# LifeBoardV1.net
KiCad netlist of a schematic drawn in EAGLE
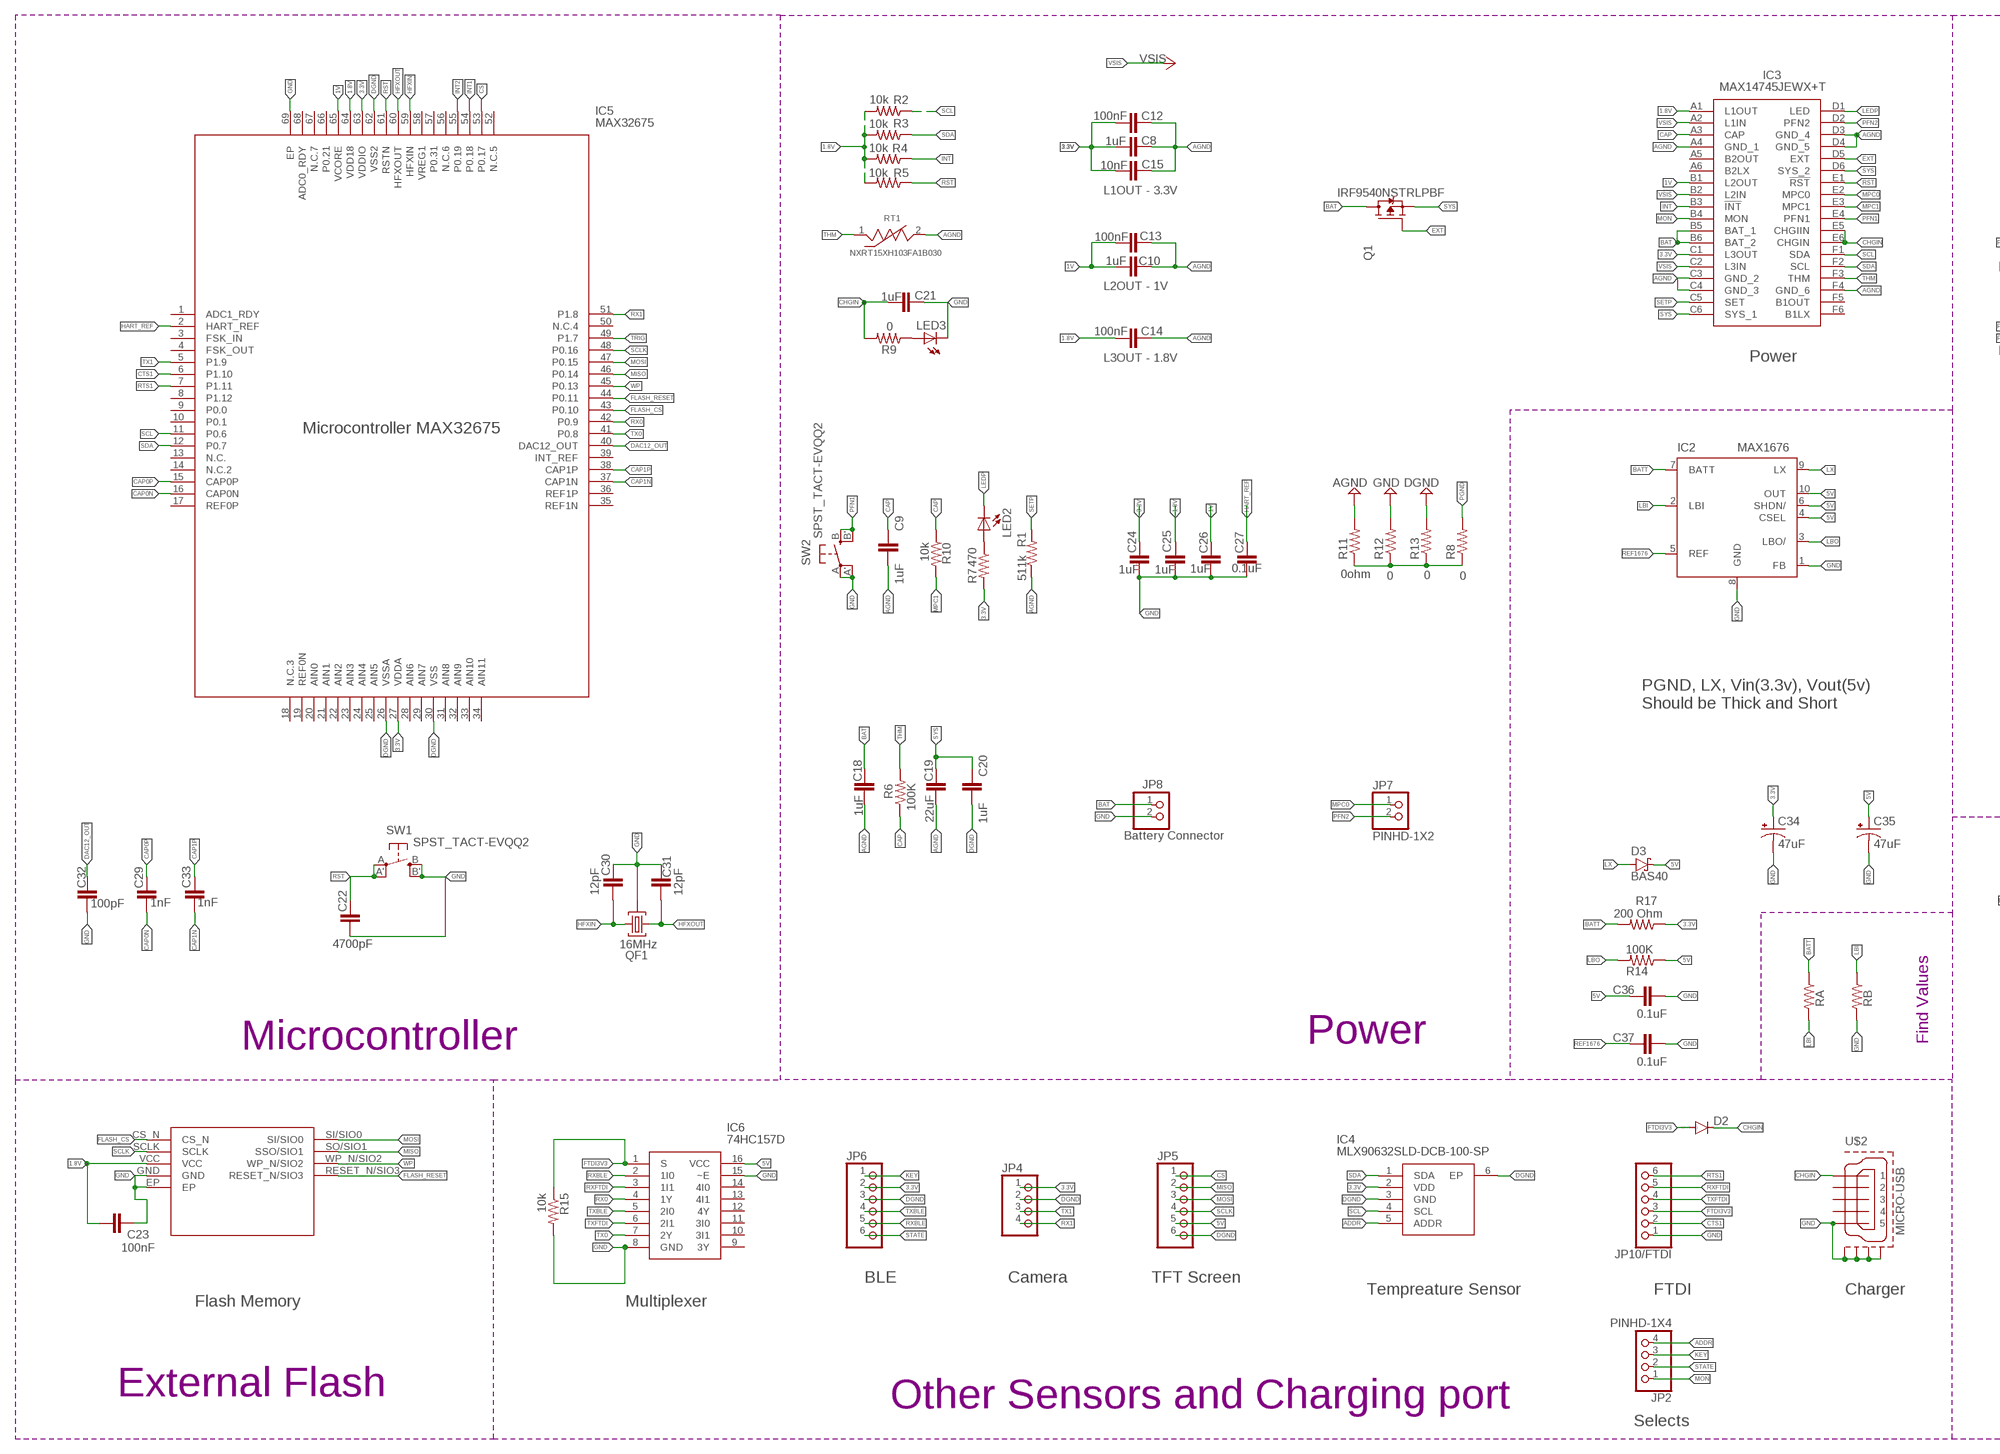
[diagram p0: schematic, sheet 1, part 1 of 2]
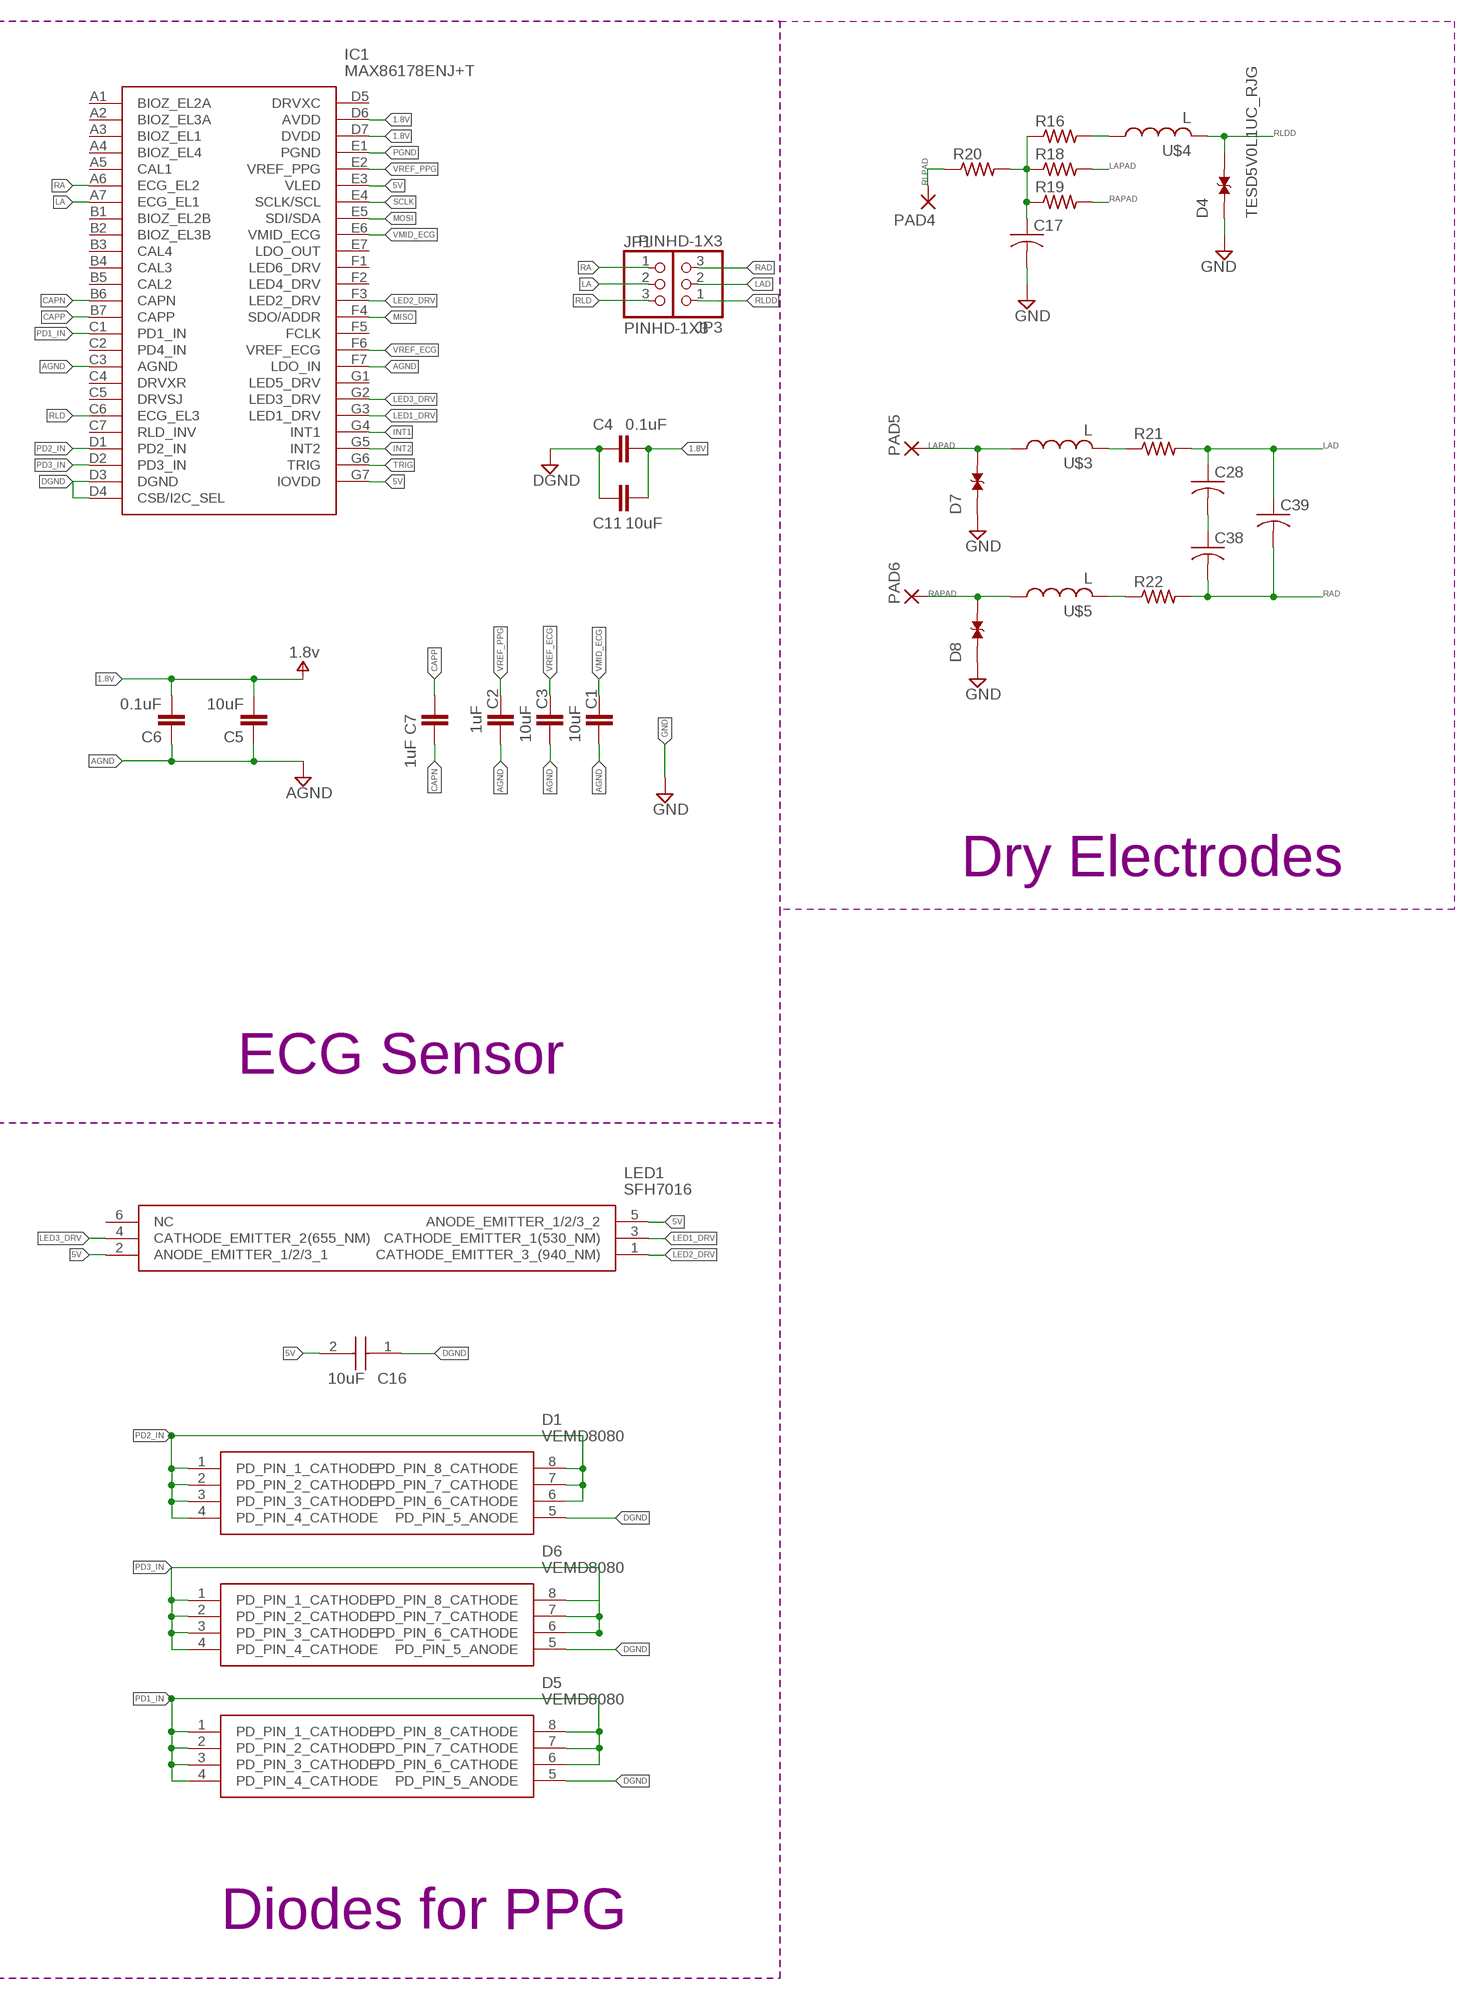
[diagram p1: schematic, sheet 1, part 2 of 2]

(export (version "E")
  (design (tool "Eeschema 10.0.6"))
  (components
    (comp (ref "C1")
      (value "10uF")
      (footprint "eagle-import:C0805")
      (libsource (lib "eagle-import") (part "C-EUC0805"))
    )
    (comp (ref "C2")
      (value "1uF")
      (footprint "eagle-import:C0805")
      (libsource (lib "eagle-import") (part "C-EUC0805"))
    )
    (comp (ref "C3")
      (value "10uF")
      (footprint "eagle-import:C0805")
      (libsource (lib "eagle-import") (part "C-EUC0805"))
    )
    (comp (ref "C4")
      (value "0.1uF")
      (footprint "eagle-import:C0805")
      (libsource (lib "eagle-import") (part "C-EUC0805"))
    )
    (comp (ref "C5")
      (value "10uF")
      (footprint "eagle-import:C0805")
      (libsource (lib "eagle-import") (part "C-EUC0805"))
    )
    (comp (ref "C6")
      (value "0.1uF")
      (footprint "eagle-import:C0805")
      (libsource (lib "eagle-import") (part "C-EUC0805"))
    )
    (comp (ref "C7")
      (value "1uF")
      (footprint "eagle-import:C0805")
      (libsource (lib "eagle-import") (part "C-EUC0805"))
    )
    (comp (ref "C8")
      (value "1uF")
      (footprint "eagle-import:C0805")
      (libsource (lib "eagle-import") (part "C-EUC0805"))
    )
    (comp (ref "C9")
      (value "1uF")
      (footprint "eagle-import:C0805")
      (libsource (lib "eagle-import") (part "C-EUC0805"))
    )
    (comp (ref "C10")
      (value "1uF")
      (footprint "eagle-import:C0805")
      (libsource (lib "eagle-import") (part "C-EUC0805"))
    )
    (comp (ref "C11")
      (value "10uF")
      (footprint "eagle-import:C0805")
      (libsource (lib "eagle-import") (part "C-EUC0805"))
    )
    (comp (ref "C12")
      (value "100nF")
      (footprint "eagle-import:C0805")
      (libsource (lib "eagle-import") (part "C-EUC0805"))
    )
    (comp (ref "C13")
      (value "100nF")
      (footprint "eagle-import:C0805")
      (libsource (lib "eagle-import") (part "C-EUC0805"))
    )
    (comp (ref "C14")
      (value "100nF")
      (footprint "eagle-import:C0805")
      (libsource (lib "eagle-import") (part "C-EUC0805"))
    )
    (comp (ref "C15")
      (value "10nF")
      (footprint "eagle-import:C0805")
      (libsource (lib "eagle-import") (part "C-EUC0805"))
    )
    (comp (ref "C16")
      (value "10uF")
      (footprint "eagle-import:CAPC1608X90N")
      (fields
        (field (name "ARROW_PART_NUMBER") "GRM188R61E106MA73L")
        (field (name "MOUSER_PART_NUMBER") "81-GRM188R61E106MA3L")
      )
      (libsource (lib "eagle-import") (part "GRM188R61E106MA73L"))
    )
    (comp (ref "C17")
      (value "C-US025-024X044")
      (footprint "eagle-import:C025-024X044")
      (libsource (lib "eagle-import") (part "C-US025-024X044"))
    )
    (comp (ref "C18")
      (value "1uF")
      (footprint "eagle-import:C0805")
      (libsource (lib "eagle-import") (part "C-EUC0805"))
    )
    (comp (ref "C19")
      (value "22uF")
      (footprint "eagle-import:C0805")
      (libsource (lib "eagle-import") (part "C-EUC0805"))
    )
    (comp (ref "C20")
      (value "1uF")
      (footprint "eagle-import:C0805")
      (libsource (lib "eagle-import") (part "C-EUC0805"))
    )
    (comp (ref "C21")
      (value "1uF")
      (footprint "eagle-import:C0805")
      (libsource (lib "eagle-import") (part "C-EUC0805"))
    )
    (comp (ref "C22")
      (value "4700pF")
      (footprint "eagle-import:C0805")
      (libsource (lib "eagle-import") (part "C-EUC0805"))
    )
    (comp (ref "C23")
      (value "100nF")
      (footprint "eagle-import:C0805")
      (libsource (lib "eagle-import") (part "C-EUC0805"))
    )
    (comp (ref "C24")
      (value "1uF")
      (footprint "eagle-import:C0805")
      (libsource (lib "eagle-import") (part "C-EUC0805"))
    )
    (comp (ref "C25")
      (value "1uF")
      (footprint "eagle-import:C0805")
      (libsource (lib "eagle-import") (part "C-EUC0805"))
    )
    (comp (ref "C26")
      (value "1uF")
      (footprint "eagle-import:C0805")
      (libsource (lib "eagle-import") (part "C-EUC0805"))
    )
    (comp (ref "C27")
      (value "0.1uF")
      (footprint "eagle-import:C0805")
      (libsource (lib "eagle-import") (part "C-EUC0805"))
    )
    (comp (ref "C28")
      (value "C-US025-024X044")
      (footprint "eagle-import:C025-024X044")
      (libsource (lib "eagle-import") (part "C-US025-024X044"))
    )
    (comp (ref "C29")
      (value "1nF")
      (footprint "eagle-import:C0805")
      (libsource (lib "eagle-import") (part "C-EUC0805"))
    )
    (comp (ref "C30")
      (value "12pF")
      (footprint "eagle-import:C0805")
      (libsource (lib "eagle-import") (part "C-EUC0805"))
    )
    (comp (ref "C31")
      (value "12pF")
      (footprint "eagle-import:C0805")
      (libsource (lib "eagle-import") (part "C-EUC0805"))
    )
    (comp (ref "C32")
      (value "100pF")
      (footprint "eagle-import:C0805")
      (libsource (lib "eagle-import") (part "C-EUC0805"))
    )
    (comp (ref "C33")
      (value "1nF")
      (footprint "eagle-import:C0805")
      (libsource (lib "eagle-import") (part "C-EUC0805"))
    )
    (comp (ref "C34")
      (value "47uF")
      (footprint "eagle-import:153CLV-0405")
      (libsource (lib "eagle-import") (part "CPOL-US153CLV-0405"))
    )
    (comp (ref "C35")
      (value "47uF")
      (footprint "eagle-import:153CLV-0405")
      (libsource (lib "eagle-import") (part "CPOL-US153CLV-0405"))
    )
    (comp (ref "C36")
      (value "0.1uF")
      (footprint "eagle-import:C0805")
      (libsource (lib "eagle-import") (part "C-EUC0805"))
    )
    (comp (ref "C37")
      (value "0.1uF")
      (footprint "eagle-import:C0805")
      (libsource (lib "eagle-import") (part "C-EUC0805"))
    )
    (comp (ref "C38")
      (value "C-US025-024X044")
      (footprint "eagle-import:C025-024X044")
      (libsource (lib "eagle-import") (part "C-US025-024X044"))
    )
    (comp (ref "C39")
      (value "C-US025-024X044")
      (footprint "eagle-import:C025-024X044")
      (libsource (lib "eagle-import") (part "C-US025-024X044"))
    )
    (comp (ref "D1")
      (value "VEMD8080")
      (footprint "eagle-import:VEMD8080")
      (fields (field (name "MOUSER_PART_NUMBER") "78-VEMD8080"))
      (libsource (lib "eagle-import") (part "VEMD8080"))
    )
    (comp (ref "D2")
      (value "CGRM4001-G")
      (footprint "eagle-import:SOD-123_MINI-SMA")
      (libsource (lib "eagle-import") (part "CGRM400-G1"))
    )
    (comp (ref "D3")
      (value "BAS40")
      (footprint "eagle-import:SOT23")
      (libsource (lib "eagle-import") (part "BAS40"))
    )
    (comp (ref "D4")
      (value "TESD5V0L1UC_RJG")
      (footprint "eagle-import:DIO_TESD5V0L1UC_RJG")
      (fields (field (name "MF") "Taiwan Semiconductor Corporation") (field (name "MP") "TESD5V0L1UC RJG"))
      (libsource (lib "eagle-import") (part "TESD5V0L1UC_RJG"))
    )
    (comp (ref "D5")
      (value "VEMD8080")
      (footprint "eagle-import:VEMD8080")
      (fields (field (name "MOUSER_PART_NUMBER") "78-VEMD8080"))
      (libsource (lib "eagle-import") (part "VEMD8080"))
    )
    (comp (ref "D6")
      (value "VEMD8080")
      (footprint "eagle-import:VEMD8080")
      (fields (field (name "MOUSER_PART_NUMBER") "78-VEMD8080"))
      (libsource (lib "eagle-import") (part "VEMD8080"))
    )
    (comp (ref "D7")
      (value "TESD5V0L1UC_RJG")
      (footprint "eagle-import:DIO_TESD5V0L1UC_RJG")
      (fields (field (name "MF") "Taiwan Semiconductor Corporation") (field (name "MP") "TESD5V0L1UC RJG"))
      (libsource (lib "eagle-import") (part "TESD5V0L1UC_RJG"))
    )
    (comp (ref "D8")
      (value "TESD5V0L1UC_RJG")
      (footprint "eagle-import:DIO_TESD5V0L1UC_RJG")
      (fields (field (name "MF") "Taiwan Semiconductor Corporation") (field (name "MP") "TESD5V0L1UC RJG"))
      (libsource (lib "eagle-import") (part "TESD5V0L1UC_RJG"))
    )
    (comp (ref "IC1")
      (value "MAX86178ENJ+T")
      (footprint "eagle-import:BGA49C35P7X7_277X257X50")
      (fields (field (name "MOUSER_PART_NUMBER") "700-MAX86178ENJ+T"))
      (libsource (lib "eagle-import") (part "MAX86178ENJ+T"))
    )
    (comp (ref "IC2")
      (value "MAX1676")
      (footprint "eagle-import:UMAX10")
      (fields (field (name "MF") "Maxim Integrated"))
      (libsource (lib "eagle-import") (part "MAX1676"))
    )
    (comp (ref "IC3")
      (value "MAX14745JEWX+T")
      (footprint "eagle-import:BGA36C40P6X6_269X244X69")
      (fields (field (name "MOUSER_PART_NUMBER") "700-MAX14745JEWX+T"))
      (libsource (lib "eagle-import") (part "MAX14745JEWX+T"))
    )
    (comp (ref "IC4")
      (value "MLX90632SLD-DCB-100-SP")
      (footprint "eagle-import:MLX90632SLDDCB100SP")
      (fields (field (name "MOUSER_PART_NUMBER") "482-90632SLDDCB100SP"))
      (libsource (lib "eagle-import") (part "MLX90632SLD-DCB-100-SP"))
    )
    (comp (ref "IC5")
      (value "MAX32675")
      (footprint "eagle-import:QFN40P800X800X100-69N")
      (fields
        (field (name "ARROW_PART_NUMBER") "CY8C5268LTI-LP030")
        (field (name "MOUSER_PART_NUMBER") "727-CY8C5268LTILP030")
      )
      (libsource (lib "eagle-import") (part "CY8C5268LTI-LP030"))
    )
    (comp (ref "IC6")
      (value "74HC157D")
      (footprint "eagle-import:SOIC127P600X175-16N")
      (fields (field (name "MOUSER_PART_NUMBER") "771-74HC157D"))
      (libsource (lib "eagle-import") (part "74HC157D"))
    )
    (comp (ref "JP1")
      (value "PINHD-1X3")
      (footprint "eagle-import:1X03")
      (libsource (lib "eagle-import") (part "PINHD-1X3"))
    )
    (comp (ref "JP2")
      (value "PINHD-1X4")
      (footprint "eagle-import:1X04")
      (libsource (lib "eagle-import") (part "PINHD-1X4"))
    )
    (comp (ref "JP3")
      (value "PINHD-1X3")
      (footprint "eagle-import:1X03")
      (libsource (lib "eagle-import") (part "PINHD-1X3"))
    )
    (comp (ref "JP4")
      (value "PINHD-1X4")
      (footprint "eagle-import:1X04")
      (libsource (lib "eagle-import") (part "pinhead_325_PINHD-1X4"))
    )
    (comp (ref "JP5")
      (value "PINHD-1X6")
      (footprint "eagle-import:1X06")
      (libsource (lib "eagle-import") (part "PINHD-1X6"))
    )
    (comp (ref "JP6")
      (value "PINHD-1X6")
      (footprint "eagle-import:1X06")
      (libsource (lib "eagle-import") (part "PINHD-1X6"))
    )
    (comp (ref "JP7")
      (value "PINHD-1X2")
      (footprint "eagle-import:1X02")
      (libsource (lib "eagle-import") (part "PINHD-1X2"))
    )
    (comp (ref "JP8")
      (value "Battery Connector")
      (footprint "eagle-import:1X02")
      (libsource (lib "eagle-import") (part "PINHD-1X2"))
    )
    (comp (ref "JP10/FTDI")
      (value "PINHD-1X6")
      (footprint "eagle-import:1X06")
      (libsource (lib "eagle-import") (part "PINHD-1X6"))
    )
    (comp (ref "LED1")
      (value "SFH7016")
      (footprint "eagle-import:SFH7016")
      (libsource (lib "eagle-import") (part "SFH7016"))
    )
    (comp (ref "LED2")
      (value "LEDCHIPLED_1206")
      (footprint "eagle-import:CHIPLED_1206")
      (libsource (lib "eagle-import") (part "LEDCHIPLED_1206"))
    )
    (comp (ref "LED3")
      (value "LEDCHIPLED_1206")
      (footprint "eagle-import:CHIPLED_1206")
      (libsource (lib "eagle-import") (part "LEDCHIPLED_1206"))
    )
    (comp (ref "PAD4")
      (value "SMD5")
      (footprint "eagle-import:SMD2,54-5,08")
      (libsource (lib "eagle-import") (part "SMD5"))
    )
    (comp (ref "PAD5")
      (value "SMD5")
      (footprint "eagle-import:SMD2,54-5,08")
      (libsource (lib "eagle-import") (part "SMD5"))
    )
    (comp (ref "PAD6")
      (value "SMD5")
      (footprint "eagle-import:SMD2,54-5,08")
      (libsource (lib "eagle-import") (part "SMD5"))
    )
    (comp (ref "Q1")
      (value "IRF9540NSTRLPBF")
      (footprint "eagle-import:DPAK254P1524X483-4_3N")
      (fields (field (name "MF") "Infineon"))
      (libsource (lib "eagle-import") (part "IRF9540NSTRLPBF"))
    )
    (comp (ref "QF1")
      (value "16MHz")
      (footprint "eagle-import:HC49U")
      (libsource (lib "eagle-import") (part "8M10AHC49T"))
    )
    (comp (ref "R1")
      (value "511k")
      (footprint "eagle-import:M1206")
      (libsource (lib "eagle-import") (part "R-US_M1206"))
    )
    (comp (ref "R2")
      (value "10k")
      (footprint "eagle-import:M1206")
      (libsource (lib "eagle-import") (part "R-US_M1206"))
    )
    (comp (ref "R3")
      (value "10k")
      (footprint "eagle-import:M1206")
      (libsource (lib "eagle-import") (part "R-US_M1206"))
    )
    (comp (ref "R4")
      (value "10k")
      (footprint "eagle-import:M1206")
      (libsource (lib "eagle-import") (part "R-US_M1206"))
    )
    (comp (ref "R5")
      (value "10k")
      (footprint "eagle-import:M1206")
      (libsource (lib "eagle-import") (part "R-US_M1206"))
    )
    (comp (ref "R6")
      (value "100K")
      (footprint "eagle-import:M1206")
      (libsource (lib "eagle-import") (part "R-US_M1206"))
    )
    (comp (ref "R7")
      (value "470")
      (footprint "eagle-import:M1206")
      (libsource (lib "eagle-import") (part "R-US_M1206"))
    )
    (comp (ref "R8")
      (value "0")
      (footprint "eagle-import:R1206")
      (libsource (lib "eagle-import") (part "R-US_R1206"))
    )
    (comp (ref "R9")
      (value "0")
      (footprint "eagle-import:R1206")
      (libsource (lib "eagle-import") (part "R-US_R1206"))
    )
    (comp (ref "R10")
      (value "10k")
      (footprint "eagle-import:M1206")
      (libsource (lib "eagle-import") (part "R-US_M1206"))
    )
    (comp (ref "R11")
      (value "0ohm")
      (footprint "eagle-import:R1206")
      (libsource (lib "eagle-import") (part "R-US_R1206"))
    )
    (comp (ref "R12")
      (value "0")
      (footprint "eagle-import:R1206")
      (libsource (lib "eagle-import") (part "R-US_R1206"))
    )
    (comp (ref "R13")
      (value "0")
      (footprint "eagle-import:R1206")
      (libsource (lib "eagle-import") (part "R-US_R1206"))
    )
    (comp (ref "R14")
      (value "100K")
      (footprint "eagle-import:R1206")
      (libsource (lib "eagle-import") (part "R-US_R1206"))
    )
    (comp (ref "R15")
      (value "10k")
      (footprint "eagle-import:M1206")
      (libsource (lib "eagle-import") (part "R-US_M1206"))
    )
    (comp (ref "R16")
      (value "R-US_0207/10")
      (footprint "eagle-import:0207_10")
      (libsource (lib "eagle-import") (part "R-US_0207/10"))
    )
    (comp (ref "R17")
      (value "200 Ohm")
      (footprint "eagle-import:R1206")
      (libsource (lib "eagle-import") (part "R-US_R1206"))
    )
    (comp (ref "R18")
      (value "R-US_0207/10")
      (footprint "eagle-import:0207_10")
      (libsource (lib "eagle-import") (part "R-US_0207/10"))
    )
    (comp (ref "R19")
      (value "R-US_0207/10")
      (footprint "eagle-import:0207_10")
      (libsource (lib "eagle-import") (part "R-US_0207/10"))
    )
    (comp (ref "R20")
      (value "R-US_0207/10")
      (footprint "eagle-import:0207_10")
      (libsource (lib "eagle-import") (part "R-US_0207/10"))
    )
    (comp (ref "R21")
      (value "R-US_0207/10")
      (footprint "eagle-import:0207_10")
      (libsource (lib "eagle-import") (part "R-US_0207/10"))
    )
    (comp (ref "R22")
      (value "R-US_0207/10")
      (footprint "eagle-import:0207_10")
      (libsource (lib "eagle-import") (part "R-US_0207/10"))
    )
    (comp (ref "RA")
      (value "R-US_R1206")
      (footprint "eagle-import:R1206")
      (libsource (lib "eagle-import") (part "R-US_R1206"))
    )
    (comp (ref "RB")
      (value "R-US_R1206")
      (footprint "eagle-import:R1206")
      (libsource (lib "eagle-import") (part "R-US_R1206"))
    )
    (comp (ref "RT1")
      (value "NXRT15XH103FA1B030")
      (footprint "eagle-import:THERM_NXRT15XH103FA1B030")
      (fields (field (name "MF") "Murata"))
      (libsource (lib "eagle-import") (part "NXRT15XH103FA1B030"))
    )
    (comp (ref "SW1")
      (value "SPST_TACT-EVQQ2")
      (footprint "eagle-import:EVQ-Q2")
      (libsource (lib "eagle-import") (part "SPST_TACT-EVQQ2"))
    )
    (comp (ref "SW2")
      (value "SPST_TACT-EVQQ2")
      (footprint "eagle-import:EVQ-Q2")
      (libsource (lib "eagle-import") (part "SPST_TACT-EVQQ2"))
    )
    (comp (ref "U$1")
      (value "FLASH")
      (footprint "eagle-import:SON127P600X800X80-9N")
      (libsource (lib "eagle-import") (part "FLASH"))
    )
    (comp (ref "U$2")
      (value "MICRO-USB")
      (footprint "eagle-import:47589-0001")
      (libsource (lib "eagle-import") (part "MICRO-USB-RECEPTACLE47589-0001"))
    )
    (comp (ref "U$3") (value "L") (footprint "eagle-import:6000") (libsource (lib "eagle-import") (part "L")))
    (comp (ref "U$4") (value "L") (footprint "eagle-import:6000") (libsource (lib "eagle-import") (part "L")))
    (comp (ref "U$5") (value "L") (footprint "eagle-import:6000") (libsource (lib "eagle-import") (part "L")))
  )
  (nets
    (net (code "1") (name "/LAPAD") (class "Default")
      (node (ref "D7") (pin "2") (pinfunction "2_2") (pintype "passive"))
      (node (ref "PAD5") (pin "1") (pinfunction "P_1") (pintype "passive"))
      (node (ref "R18") (pin "2") (pinfunction "2_2") (pintype "passive"))
      (node (ref "U$3") (pin "1") (pinfunction "1_1") (pintype "passive"))
    )
    (net (code "2") (name "/RAPAD") (class "Default")
      (node (ref "D8") (pin "2") (pinfunction "2_2") (pintype "passive"))
      (node (ref "PAD6") (pin "1") (pinfunction "P_1") (pintype "passive"))
      (node (ref "R19") (pin "2") (pinfunction "2_2") (pintype "passive"))
      (node (ref "U$5") (pin "1") (pinfunction "1_1") (pintype "passive"))
    )
    (net (code "3") (name "/RLPAD") (class "Default")
      (node (ref "PAD4") (pin "1") (pinfunction "P_1") (pintype "passive"))
      (node (ref "R20") (pin "1") (pinfunction "1_1") (pintype "passive"))
    )
    (net (code "4") (name "1.8V") (class "Default")
      (node (ref "C11") (pin "2") (pinfunction "2_2") (pintype "passive"))
      (node (ref "C14") (pin "2") (pinfunction "2_2") (pintype "passive"))
      (node (ref "C23") (pin "1") (pinfunction "1_1") (pintype "passive"))
      (node (ref "C25") (pin "1") (pinfunction "1_1") (pintype "passive"))
      (node (ref "C4") (pin "2") (pinfunction "2_2") (pintype "passive"))
      (node (ref "C5") (pin "2") (pinfunction "2_2") (pintype "passive"))
      (node (ref "C6") (pin "2") (pinfunction "2_2") (pintype "passive"))
      (node (ref "IC1") (pin "D6") (pinfunction "AVDD_D6") (pintype "bidirectional"))
      (node (ref "IC1") (pin "D7") (pinfunction "DVDD_D7") (pintype "bidirectional"))
      (node (ref "IC3") (pin "A1") (pinfunction "L1OUT_A1") (pintype "bidirectional"))
      (node (ref "IC5") (pin "64") (pinfunction "VDD18_64") (pintype "bidirectional"))
      (node (ref "R2") (pin "2") (pinfunction "2_2") (pintype "passive"))
      (node (ref "R3") (pin "2") (pinfunction "2_2") (pintype "passive"))
      (node (ref "R4") (pin "2") (pinfunction "2_2") (pintype "passive"))
      (node (ref "R5") (pin "2") (pinfunction "2_2") (pintype "passive"))
      (node (ref "U$1") (pin "VCC") (pinfunction "VCC_VCC") (pintype "bidirectional"))
    )
    (net (code "5") (name "1V") (class "Default")
      (node (ref "C10") (pin "2") (pinfunction "2_2") (pintype "passive"))
      (node (ref "C13") (pin "2") (pinfunction "2_2") (pintype "passive"))
      (node (ref "C26") (pin "1") (pinfunction "1_1") (pintype "passive"))
      (node (ref "IC3") (pin "B1") (pinfunction "L2OUT_B1") (pintype "bidirectional"))
      (node (ref "IC5") (pin "65") (pinfunction "VCORE_65") (pintype "bidirectional"))
    )
    (net (code "6") (name "3.3V") (class "Default")
      (node (ref "C12") (pin "2") (pinfunction "2_2") (pintype "passive"))
      (node (ref "C15") (pin "2") (pinfunction "2_2") (pintype "passive"))
      (node (ref "C24") (pin "1") (pinfunction "1_1") (pintype "passive"))
      (node (ref "C34") (pin "+") (pinfunction "+_+") (pintype "passive"))
      (node (ref "C8") (pin "2") (pinfunction "2_2") (pintype "passive"))
      (node (ref "IC3") (pin "C1") (pinfunction "L3OUT_C1") (pintype "bidirectional"))
      (node (ref "IC4") (pin "2") (pinfunction "VDD_2") (pintype "bidirectional"))
      (node (ref "IC5") (pin "27") (pinfunction "VDDA_27") (pintype "bidirectional"))
      (node (ref "IC5") (pin "63") (pinfunction "VDDIO_63") (pintype "bidirectional"))
      (node (ref "JP4") (pin "1") (pinfunction "1_1") (pintype "passive"))
      (node (ref "JP6") (pin "2") (pinfunction "2_2") (pintype "passive"))
      (node (ref "R17") (pin "1") (pinfunction "1_1") (pintype "passive"))
      (node (ref "R7") (pin "2") (pinfunction "2_2") (pintype "passive"))
    )
    (net (code "7") (name "5V") (class "Default")
      (node (ref "C16") (pin "2") (pinfunction "2_2") (pintype "bidirectional"))
      (node (ref "C35") (pin "+") (pinfunction "+_+") (pintype "passive"))
      (node (ref "C36") (pin "1") (pinfunction "1_1") (pintype "passive"))
      (node (ref "D3") (pin "3") (pinfunction "C_3") (pintype "passive"))
      (node (ref "IC1") (pin "E3") (pinfunction "VLED_E3") (pintype "bidirectional"))
      (node (ref "IC1") (pin "G7") (pinfunction "IOVDD_G7") (pintype "bidirectional"))
      (node (ref "IC2") (pin "10") (pinfunction "OUT_10") (pintype "output"))
      (node (ref "IC2") (pin "4") (pinfunction "CSEL_4") (pintype "input"))
      (node (ref "IC2") (pin "6") (pinfunction "SHDN/_6") (pintype "input"))
      (node (ref "IC6") (pin "16") (pinfunction "VCC_16") (pintype "bidirectional"))
      (node (ref "JP5") (pin "5") (pinfunction "5_5") (pintype "passive"))
      (node (ref "LED1") (pin "2") (pinfunction "ANODE_EMITTER_1/2/3_1_2") (pintype "bidirectional"))
      (node (ref "LED1") (pin "5") (pinfunction "ANODE_EMITTER_1/2/3_2_5") (pintype "bidirectional"))
      (node (ref "R14") (pin "1") (pinfunction "1_1") (pintype "passive"))
    )
    (net (code "8") (name "ADDR") (class "Default")
      (node (ref "IC4") (pin "5") (pinfunction "ADDR_5") (pintype "bidirectional"))
      (node (ref "JP2") (pin "4") (pinfunction "4_4") (pintype "passive"))
    )
    (net (code "9") (name "AGND") (class "Default")
      (node (ref "C1") (pin "1") (pinfunction "1_1") (pintype "passive"))
      (node (ref "C10") (pin "1") (pinfunction "1_1") (pintype "passive"))
      (node (ref "C12") (pin "1") (pinfunction "1_1") (pintype "passive"))
      (node (ref "C13") (pin "1") (pinfunction "1_1") (pintype "passive"))
      (node (ref "C14") (pin "1") (pinfunction "1_1") (pintype "passive"))
      (node (ref "C15") (pin "1") (pinfunction "1_1") (pintype "passive"))
      (node (ref "C18") (pin "2") (pinfunction "2_2") (pintype "passive"))
      (node (ref "C19") (pin "2") (pinfunction "2_2") (pintype "passive"))
      (node (ref "C2") (pin "1") (pinfunction "1_1") (pintype "passive"))
      (node (ref "C3") (pin "1") (pinfunction "1_1") (pintype "passive"))
      (node (ref "C5") (pin "1") (pinfunction "1_1") (pintype "passive"))
      (node (ref "C6") (pin "1") (pinfunction "1_1") (pintype "passive"))
      (node (ref "C8") (pin "1") (pinfunction "1_1") (pintype "passive"))
      (node (ref "C9") (pin "2") (pinfunction "2_2") (pintype "passive"))
      (node (ref "IC1") (pin "C3") (pinfunction "AGND_C3") (pintype "bidirectional"))
      (node (ref "IC1") (pin "F7") (pinfunction "LDO_IN_F7") (pintype "bidirectional"))
      (node (ref "IC3") (pin "A4") (pinfunction "GND_1_A4") (pintype "bidirectional"))
      (node (ref "IC3") (pin "C3") (pinfunction "GND_2_C3") (pintype "bidirectional"))
      (node (ref "IC3") (pin "C4") (pinfunction "GND_3_C4") (pintype "bidirectional"))
      (node (ref "IC3") (pin "D3") (pinfunction "GND_4_D3") (pintype "bidirectional"))
      (node (ref "IC3") (pin "D4") (pinfunction "GND_5_D4") (pintype "bidirectional"))
      (node (ref "IC3") (pin "F4") (pinfunction "GND_6_F4") (pintype "bidirectional"))
      (node (ref "R1") (pin "1") (pinfunction "1_1") (pintype "passive"))
      (node (ref "R11") (pin "2") (pinfunction "2_2") (pintype "passive"))
      (node (ref "RT1") (pin "2") (pinfunction "2_2") (pintype "passive"))
    )
    (net (code "10") (name "BAT") (class "Default")
      (node (ref "C18") (pin "1") (pinfunction "1_1") (pintype "passive"))
      (node (ref "IC3") (pin "B5") (pinfunction "BAT_1_B5") (pintype "bidirectional"))
      (node (ref "IC3") (pin "B6") (pinfunction "BAT_2_B6") (pintype "bidirectional"))
      (node (ref "JP8") (pin "1") (pinfunction "1_1") (pintype "passive"))
      (node (ref "Q1") (pin "4") (pinfunction "D_4") (pintype "passive"))
    )
    (net (code "11") (name "BATT") (class "Default")
      (node (ref "IC2") (pin "7") (pinfunction "BATT_7") (pintype "input"))
      (node (ref "R17") (pin "2") (pinfunction "2_2") (pintype "passive"))
      (node (ref "RA") (pin "1") (pinfunction "1_1") (pintype "passive"))
    )
    (net (code "12") (name "CAP") (class "Default")
      (node (ref "C9") (pin "1") (pinfunction "1_1") (pintype "passive"))
      (node (ref "IC3") (pin "A3") (pinfunction "CAP_A3") (pintype "bidirectional"))
      (node (ref "R10") (pin "1") (pinfunction "1_1") (pintype "passive"))
      (node (ref "R6") (pin "1") (pinfunction "1_1") (pintype "passive"))
    )
    (net (code "13") (name "CAP0N") (class "Default")
      (node (ref "C29") (pin "2") (pinfunction "2_2") (pintype "passive"))
      (node (ref "IC5") (pin "16") (pinfunction "CAP0N_16") (pintype "bidirectional"))
    )
    (net (code "14") (name "CAP0P") (class "Default")
      (node (ref "C29") (pin "1") (pinfunction "1_1") (pintype "passive"))
      (node (ref "IC5") (pin "15") (pinfunction "CAP0P_15") (pintype "bidirectional"))
    )
    (net (code "15") (name "CAP1N") (class "Default")
      (node (ref "C33") (pin "1") (pinfunction "1_1") (pintype "passive"))
      (node (ref "IC5") (pin "37") (pinfunction "CAP1N_37") (pintype "bidirectional"))
    )
    (net (code "16") (name "CAP1P") (class "Default")
      (node (ref "C33") (pin "2") (pinfunction "2_2") (pintype "passive"))
      (node (ref "IC5") (pin "38") (pinfunction "CAP1P_38") (pintype "bidirectional"))
    )
    (net (code "17") (name "CAPN") (class "Default")
      (node (ref "C7") (pin "2") (pinfunction "2_2") (pintype "passive"))
      (node (ref "IC1") (pin "B6") (pinfunction "CAPN_B6") (pintype "bidirectional"))
    )
    (net (code "18") (name "CAPP") (class "Default")
      (node (ref "C7") (pin "1") (pinfunction "1_1") (pintype "passive"))
      (node (ref "IC1") (pin "B7") (pinfunction "CAPP_B7") (pintype "bidirectional"))
    )
    (net (code "19") (name "CHGIN") (class "Default")
      (node (ref "C21") (pin "2") (pinfunction "2_2") (pintype "passive"))
      (node (ref "D2") (pin "C") (pinfunction "C_C") (pintype "passive"))
      (node (ref "IC3") (pin "E5") (pinfunction "CHGIIN_E5") (pintype "bidirectional"))
      (node (ref "IC3") (pin "E6") (pinfunction "CHGIN_E6") (pintype "bidirectional"))
      (node (ref "R9") (pin "2") (pinfunction "2_2") (pintype "passive"))
      (node (ref "U$2") (pin "1") (pinfunction "1_1") (pintype "input"))
    )
    (net (code "20") (name "CS") (class "Default")
      (node (ref "IC5") (pin "53") (pinfunction "P0.17_53") (pintype "bidirectional"))
      (node (ref "JP5") (pin "1") (pinfunction "1_1") (pintype "passive"))
    )
    (net (code "21") (name "CTS1") (class "Default")
      (node (ref "IC5") (pin "6") (pinfunction "P1.10_6") (pintype "bidirectional"))
      (node (ref "JP10/FTDI") (pin "2") (pinfunction "2_2") (pintype "passive"))
    )
    (net (code "22") (name "DAC12_OUT") (class "Default")
      (node (ref "C32") (pin "1") (pinfunction "1_1") (pintype "passive"))
      (node (ref "IC5") (pin "40") (pinfunction "DAC12_OUT_40") (pintype "bidirectional"))
    )
    (net (code "23") (name "DGND") (class "Default")
      (node (ref "C11") (pin "1") (pinfunction "1_1") (pintype "passive"))
      (node (ref "C16") (pin "1") (pinfunction "1_1") (pintype "bidirectional"))
      (node (ref "C20") (pin "2") (pinfunction "2_2") (pintype "passive"))
      (node (ref "C4") (pin "1") (pinfunction "1_1") (pintype "passive"))
      (node (ref "D1") (pin "5") (pinfunction "PD_PIN_5_ANODE_5") (pintype "bidirectional"))
      (node (ref "D5") (pin "5") (pinfunction "PD_PIN_5_ANODE_5") (pintype "bidirectional"))
      (node (ref "D6") (pin "5") (pinfunction "PD_PIN_5_ANODE_5") (pintype "bidirectional"))
      (node (ref "IC1") (pin "D3") (pinfunction "DGND_D3") (pintype "bidirectional"))
      (node (ref "IC1") (pin "D4") (pinfunction "CSB/I2C_SEL_D4") (pintype "bidirectional"))
      (node (ref "IC4") (pin "3") (pinfunction "GND_3") (pintype "bidirectional"))
      (node (ref "IC4") (pin "6") (pinfunction "EP_6") (pintype "bidirectional"))
      (node (ref "IC5") (pin "26") (pinfunction "VSSA_26") (pintype "bidirectional"))
      (node (ref "IC5") (pin "30") (pinfunction "VSS_30") (pintype "bidirectional"))
      (node (ref "IC5") (pin "62") (pinfunction "VSS2_62") (pintype "bidirectional"))
      (node (ref "JP4") (pin "2") (pinfunction "2_2") (pintype "passive"))
      (node (ref "JP5") (pin "6") (pinfunction "6_6") (pintype "passive"))
      (node (ref "JP6") (pin "3") (pinfunction "3_3") (pintype "passive"))
      (node (ref "R13") (pin "2") (pinfunction "2_2") (pintype "passive"))
    )
    (net (code "24") (name "EXT") (class "Default")
      (node (ref "IC3") (pin "D5") (pinfunction "EXT_D5") (pintype "bidirectional"))
      (node (ref "Q1") (pin "1") (pinfunction "G_1") (pintype "passive"))
    )
    (net (code "25") (name "FLASH_CS") (class "Default")
      (node (ref "IC5") (pin "43") (pinfunction "P0.10_43") (pintype "bidirectional"))
      (node (ref "U$1") (pin "CS_N") (pinfunction "CS_N_CS_N") (pintype "bidirectional"))
    )
    (net (code "26") (name "FLASH_RESET") (class "Default")
      (node (ref "IC5") (pin "44") (pinfunction "P0.11_44") (pintype "bidirectional"))
      (node (ref "U$1") (pin "RESET_N/SIO3") (pinfunction "RESET_N/SIO3_RESET_N/SIO3") (pintype "bidirectional"))
    )
    (net (code "27") (name "FTDI3V3") (class "Default")
      (node (ref "D2") (pin "A") (pinfunction "A_A") (pintype "passive"))
      (node (ref "IC6") (pin "1") (pinfunction "S_1") (pintype "bidirectional"))
      (node (ref "JP10/FTDI") (pin "3") (pinfunction "3_3") (pintype "passive"))
      (node (ref "R15") (pin "1") (pinfunction "1_1") (pintype "passive"))
    )
    (net (code "28") (name "GND") (class "Default")
      (node (ref "C17") (pin "2") (pinfunction "2_2") (pintype "passive"))
      (node (ref "C21") (pin "1") (pinfunction "1_1") (pintype "passive"))
      (node (ref "C22") (pin "2") (pinfunction "2_2") (pintype "passive"))
      (node (ref "C23") (pin "2") (pinfunction "2_2") (pintype "passive"))
      (node (ref "C24") (pin "2") (pinfunction "2_2") (pintype "passive"))
      (node (ref "C25") (pin "2") (pinfunction "2_2") (pintype "passive"))
      (node (ref "C26") (pin "2") (pinfunction "2_2") (pintype "passive"))
      (node (ref "C27") (pin "2") (pinfunction "2_2") (pintype "passive"))
      (node (ref "C30") (pin "1") (pinfunction "1_1") (pintype "passive"))
      (node (ref "C31") (pin "1") (pinfunction "1_1") (pintype "passive"))
      (node (ref "C32") (pin "2") (pinfunction "2_2") (pintype "passive"))
      (node (ref "C34") (pin "-") (pinfunction "-_-") (pintype "passive"))
      (node (ref "C35") (pin "-") (pinfunction "-_-") (pintype "passive"))
      (node (ref "C36") (pin "2") (pinfunction "2_2") (pintype "passive"))
      (node (ref "C37") (pin "2") (pinfunction "2_2") (pintype "passive"))
      (node (ref "D4") (pin "1") (pinfunction "1_1") (pintype "passive"))
      (node (ref "D7") (pin "1") (pinfunction "1_1") (pintype "passive"))
      (node (ref "D8") (pin "1") (pinfunction "1_1") (pintype "passive"))
      (node (ref "IC2") (pin "1") (pinfunction "FB_1") (pintype "input"))
      (node (ref "IC2") (pin "8") (pinfunction "GND_8") (pintype "power_in"))
      (node (ref "IC5") (pin "69") (pinfunction "EP_69") (pintype "bidirectional"))
      (node (ref "IC6") (pin "15") (pinfunction "~{E}_15") (pintype "bidirectional"))
      (node (ref "IC6") (pin "8") (pinfunction "GND_8") (pintype "bidirectional"))
      (node (ref "JP10/FTDI") (pin "1") (pinfunction "1_1") (pintype "passive"))
      (node (ref "JP8") (pin "2") (pinfunction "2_2") (pintype "passive"))
      (node (ref "LED3") (pin "C") (pinfunction "C_C") (pintype "passive"))
      (node (ref "QF1") (pin "2") (pinfunction "2_2") (pintype "passive"))
      (node (ref "R12") (pin "2") (pinfunction "2_2") (pintype "passive"))
      (node (ref "R15") (pin "2") (pinfunction "2_2") (pintype "passive"))
      (node (ref "RB") (pin "2") (pinfunction "2_2") (pintype "passive"))
      (node (ref "SW1") (pin "B") (pinfunction "S_B") (pintype "passive"))
      (node (ref "SW1") (pin "B'") (pinfunction "S1_B'") (pintype "passive"))
      (node (ref "SW2") (pin "A") (pinfunction "P_A") (pintype "passive"))
      (node (ref "SW2") (pin "A'") (pinfunction "P1_A'") (pintype "passive"))
      (node (ref "U$1") (pin "EP") (pinfunction "EP_EP") (pintype "bidirectional"))
      (node (ref "U$1") (pin "GND") (pinfunction "GND_GND") (pintype "bidirectional"))
      (node (ref "U$2") (pin "5") (pinfunction "5_5") (pintype "input"))
      (node (ref "U$2") (pin "CASING1") (pinfunction "GND1_CASING1") (pintype "bidirectional"))
      (node (ref "U$2") (pin "CASING2") (pinfunction "GND2_CASING2") (pintype "bidirectional"))
      (node (ref "U$2") (pin "CASING3") (pinfunction "GND3_CASING3") (pintype "bidirectional"))
      (node (ref "U$2") (pin "CASING4") (pinfunction "GND4_CASING4") (pintype "bidirectional"))
    )
    (net (code "29") (name "HART_REF") (class "Default")
      (node (ref "C27") (pin "1") (pinfunction "1_1") (pintype "passive"))
      (node (ref "IC5") (pin "2") (pinfunction "HART_REF_2") (pintype "bidirectional"))
    )
    (net (code "30") (name "HFXIN") (class "Default")
      (node (ref "C30") (pin "2") (pinfunction "2_2") (pintype "passive"))
      (node (ref "IC5") (pin "59") (pinfunction "HFXIN_59") (pintype "bidirectional"))
      (node (ref "QF1") (pin "3") (pinfunction "3_3") (pintype "passive"))
    )
    (net (code "31") (name "HFXOUT") (class "Default")
      (node (ref "C31") (pin "2") (pinfunction "2_2") (pintype "passive"))
      (node (ref "IC5") (pin "60") (pinfunction "HFXOUT_60") (pintype "bidirectional"))
      (node (ref "QF1") (pin "1") (pinfunction "1_1") (pintype "passive"))
    )
    (net (code "32") (name "INT") (class "Default")
      (node (ref "IC3") (pin "B3") (pinfunction "~{INT}_B3") (pintype "bidirectional"))
      (node (ref "R4") (pin "1") (pinfunction "1_1") (pintype "passive"))
    )
    (net (code "33") (name "INT1") (class "Default")
      (node (ref "IC1") (pin "G4") (pinfunction "INT1_G4") (pintype "bidirectional"))
      (node (ref "IC5") (pin "54") (pinfunction "P0.18_54") (pintype "bidirectional"))
    )
    (net (code "34") (name "INT2") (class "Default")
      (node (ref "IC1") (pin "G5") (pinfunction "INT2_G5") (pintype "bidirectional"))
      (node (ref "IC5") (pin "55") (pinfunction "P0.19_55") (pintype "bidirectional"))
    )
    (net (code "35") (name "KEY") (class "Default")
      (node (ref "JP2") (pin "3") (pinfunction "3_3") (pintype "passive"))
      (node (ref "JP6") (pin "1") (pinfunction "1_1") (pintype "passive"))
    )
    (net (code "36") (name "LA") (class "Default")
      (node (ref "IC1") (pin "A7") (pinfunction "ECG_EL1_A7") (pintype "bidirectional"))
      (node (ref "JP1") (pin "2") (pinfunction "2_2") (pintype "passive"))
    )
    (net (code "37") (name "LAD") (class "Default")
      (node (ref "C28") (pin "1") (pinfunction "1_1") (pintype "passive"))
      (node (ref "C39") (pin "1") (pinfunction "1_1") (pintype "passive"))
      (node (ref "JP3") (pin "2") (pinfunction "2_2") (pintype "passive"))
      (node (ref "R21") (pin "2") (pinfunction "2_2") (pintype "passive"))
    )
    (net (code "38") (name "LBI") (class "Default")
      (node (ref "IC2") (pin "2") (pinfunction "LBI_2") (pintype "input"))
      (node (ref "RA") (pin "2") (pinfunction "2_2") (pintype "passive"))
      (node (ref "RB") (pin "1") (pinfunction "1_1") (pintype "passive"))
    )
    (net (code "39") (name "LBO") (class "Default")
      (node (ref "IC2") (pin "3") (pinfunction "LBO/_3") (pintype "output"))
      (node (ref "R14") (pin "2") (pinfunction "2_2") (pintype "passive"))
    )
    (net (code "40") (name "LED1_DRV") (class "Default")
      (node (ref "IC1") (pin "G3") (pinfunction "LED1_DRV_G3") (pintype "bidirectional"))
      (node (ref "LED1") (pin "3") (pinfunction "CATHODE_EMITTER_1(530_NM)_3") (pintype "bidirectional"))
    )
    (net (code "41") (name "LED2_DRV") (class "Default")
      (node (ref "IC1") (pin "F3") (pinfunction "LED2_DRV_F3") (pintype "bidirectional"))
      (node (ref "LED1") (pin "1") (pinfunction "CATHODE_EMITTER_3_(940_NM)_1") (pintype "bidirectional"))
    )
    (net (code "42") (name "LED3_DRV") (class "Default")
      (node (ref "IC1") (pin "G2") (pinfunction "LED3_DRV_G2") (pintype "bidirectional"))
      (node (ref "LED1") (pin "4") (pinfunction "CATHODE_EMITTER_2(655_NM)_4") (pintype "bidirectional"))
    )
    (net (code "43") (name "LEDP") (class "Default")
      (node (ref "IC3") (pin "D1") (pinfunction "LED_D1") (pintype "bidirectional"))
      (node (ref "LED2") (pin "C") (pinfunction "C_C") (pintype "passive"))
    )
    (net (code "44") (name "LX") (class "Default")
      (node (ref "D3") (pin "1") (pinfunction "A_1") (pintype "passive"))
      (node (ref "IC2") (pin "9") (pinfunction "LX_9") (pintype "passive"))
    )
    (net (code "45") (name "MISO") (class "Default")
      (node (ref "IC1") (pin "F4") (pinfunction "SDO/ADDR_F4") (pintype "bidirectional"))
      (node (ref "IC5") (pin "46") (pinfunction "P0.14_46") (pintype "bidirectional"))
      (node (ref "JP5") (pin "2") (pinfunction "2_2") (pintype "passive"))
      (node (ref "U$1") (pin "SO/SIO1") (pinfunction "SSO/SIO1_SO/SIO1") (pintype "bidirectional"))
    )
    (net (code "46") (name "MON") (class "Default")
      (node (ref "IC3") (pin "B4") (pinfunction "MON_B4") (pintype "bidirectional"))
      (node (ref "JP2") (pin "1") (pinfunction "1_1") (pintype "passive"))
    )
    (net (code "47") (name "MOSI") (class "Default")
      (node (ref "IC1") (pin "E5") (pinfunction "SDI/SDA_E5") (pintype "bidirectional"))
      (node (ref "IC5") (pin "47") (pinfunction "P0.15_47") (pintype "bidirectional"))
      (node (ref "JP5") (pin "3") (pinfunction "3_3") (pintype "passive"))
      (node (ref "U$1") (pin "SI/SIO0") (pinfunction "SI/SIO0_SI/SIO0") (pintype "bidirectional"))
    )
    (net (code "48") (name "MPC0") (class "Default")
      (node (ref "IC3") (pin "E2") (pinfunction "MPC0_E2") (pintype "bidirectional"))
      (node (ref "JP7") (pin "1") (pinfunction "1_1") (pintype "passive"))
    )
    (net (code "49") (name "MPC1") (class "Default")
      (node (ref "IC3") (pin "E3") (pinfunction "MPC1_E3") (pintype "bidirectional"))
      (node (ref "R10") (pin "2") (pinfunction "2_2") (pintype "passive"))
    )
    (net (code "50") (name "Net-(C17-Pad1)") (class "Default")
      (node (ref "C17") (pin "1") (pinfunction "1_1") (pintype "passive"))
      (node (ref "R16") (pin "1") (pinfunction "1_1") (pintype "passive"))
      (node (ref "R18") (pin "1") (pinfunction "1_1") (pintype "passive"))
      (node (ref "R19") (pin "1") (pinfunction "1_1") (pintype "passive"))
      (node (ref "R20") (pin "2") (pinfunction "2_2") (pintype "passive"))
    )
    (net (code "51") (name "Net-(C28-Pad2)") (class "Default")
      (node (ref "C28") (pin "2") (pinfunction "2_2") (pintype "passive"))
      (node (ref "C38") (pin "1") (pinfunction "1_1") (pintype "passive"))
    )
    (net (code "52") (name "Net-(LED2-PadA)") (class "Default")
      (node (ref "LED2") (pin "A") (pinfunction "A_A") (pintype "passive"))
      (node (ref "R7") (pin "1") (pinfunction "1_1") (pintype "passive"))
    )
    (net (code "53") (name "Net-(LED3-PadA)") (class "Default")
      (node (ref "LED3") (pin "A") (pinfunction "A_A") (pintype "passive"))
      (node (ref "R9") (pin "1") (pinfunction "1_1") (pintype "passive"))
    )
    (net (code "54") (name "Net-(R11-Pad1)") (class "Default")
      (node (ref "R11") (pin "1") (pinfunction "1_1") (pintype "passive"))
      (node (ref "R12") (pin "1") (pinfunction "1_1") (pintype "passive"))
      (node (ref "R13") (pin "1") (pinfunction "1_1") (pintype "passive"))
      (node (ref "R8") (pin "1") (pinfunction "1_1") (pintype "passive"))
    )
    (net (code "55") (name "Net-(R16-Pad2)") (class "Default")
      (node (ref "R16") (pin "2") (pinfunction "2_2") (pintype "passive"))
      (node (ref "U$4") (pin "1") (pinfunction "1_1") (pintype "passive"))
    )
    (net (code "56") (name "Net-(R21-Pad1)") (class "Default")
      (node (ref "R21") (pin "1") (pinfunction "1_1") (pintype "passive"))
      (node (ref "U$3") (pin "2") (pinfunction "2_2") (pintype "passive"))
    )
    (net (code "57") (name "Net-(R22-Pad1)") (class "Default")
      (node (ref "R22") (pin "1") (pinfunction "1_1") (pintype "passive"))
      (node (ref "U$5") (pin "2") (pinfunction "2_2") (pintype "passive"))
    )
    (net (code "58") (name "PD1_IN") (class "Default")
      (node (ref "D5") (pin "1") (pinfunction "PD_PIN_1_CATHODE_1") (pintype "bidirectional"))
      (node (ref "D5") (pin "2") (pinfunction "PD_PIN_2_CATHODE_2") (pintype "bidirectional"))
      (node (ref "D5") (pin "3") (pinfunction "PD_PIN_3_CATHODE_3") (pintype "bidirectional"))
      (node (ref "D5") (pin "4") (pinfunction "PD_PIN_4_CATHODE_4") (pintype "bidirectional"))
      (node (ref "D5") (pin "6") (pinfunction "PD_PIN_6_CATHODE_6") (pintype "bidirectional"))
      (node (ref "D5") (pin "7") (pinfunction "PD_PIN_7_CATHODE_7") (pintype "bidirectional"))
      (node (ref "D5") (pin "8") (pinfunction "PD_PIN_8_CATHODE_8") (pintype "bidirectional"))
      (node (ref "IC1") (pin "C1") (pinfunction "PD1_IN_C1") (pintype "bidirectional"))
    )
    (net (code "59") (name "PD2_IN") (class "Default")
      (node (ref "D1") (pin "1") (pinfunction "PD_PIN_1_CATHODE_1") (pintype "bidirectional"))
      (node (ref "D1") (pin "2") (pinfunction "PD_PIN_2_CATHODE_2") (pintype "bidirectional"))
      (node (ref "D1") (pin "3") (pinfunction "PD_PIN_3_CATHODE_3") (pintype "bidirectional"))
      (node (ref "D1") (pin "4") (pinfunction "PD_PIN_4_CATHODE_4") (pintype "bidirectional"))
      (node (ref "D1") (pin "6") (pinfunction "PD_PIN_6_CATHODE_6") (pintype "bidirectional"))
      (node (ref "D1") (pin "7") (pinfunction "PD_PIN_7_CATHODE_7") (pintype "bidirectional"))
      (node (ref "D1") (pin "8") (pinfunction "PD_PIN_8_CATHODE_8") (pintype "bidirectional"))
      (node (ref "IC1") (pin "D1") (pinfunction "PD2_IN_D1") (pintype "bidirectional"))
    )
    (net (code "60") (name "PD3_IN") (class "Default")
      (node (ref "D6") (pin "1") (pinfunction "PD_PIN_1_CATHODE_1") (pintype "bidirectional"))
      (node (ref "D6") (pin "2") (pinfunction "PD_PIN_2_CATHODE_2") (pintype "bidirectional"))
      (node (ref "D6") (pin "3") (pinfunction "PD_PIN_3_CATHODE_3") (pintype "bidirectional"))
      (node (ref "D6") (pin "4") (pinfunction "PD_PIN_4_CATHODE_4") (pintype "bidirectional"))
      (node (ref "D6") (pin "6") (pinfunction "PD_PIN_6_CATHODE_6") (pintype "bidirectional"))
      (node (ref "D6") (pin "7") (pinfunction "PD_PIN_7_CATHODE_7") (pintype "bidirectional"))
      (node (ref "D6") (pin "8") (pinfunction "PD_PIN_8_CATHODE_8") (pintype "bidirectional"))
      (node (ref "IC1") (pin "D2") (pinfunction "PD3_IN_D2") (pintype "bidirectional"))
    )
    (net (code "61") (name "PFN1") (class "Default")
      (node (ref "IC3") (pin "E4") (pinfunction "PFN1_E4") (pintype "bidirectional"))
      (node (ref "SW2") (pin "B") (pinfunction "S_B") (pintype "passive"))
      (node (ref "SW2") (pin "B'") (pinfunction "S1_B'") (pintype "passive"))
    )
    (net (code "62") (name "PFN2") (class "Default")
      (node (ref "IC3") (pin "D2") (pinfunction "PFN2_D2") (pintype "bidirectional"))
      (node (ref "JP7") (pin "2") (pinfunction "2_2") (pintype "passive"))
    )
    (net (code "63") (name "PGND") (class "Default")
      (node (ref "IC1") (pin "E1") (pinfunction "PGND_E1") (pintype "bidirectional"))
      (node (ref "R8") (pin "2") (pinfunction "2_2") (pintype "passive"))
    )
    (net (code "64") (name "RA") (class "Default")
      (node (ref "IC1") (pin "A6") (pinfunction "ECG_EL2_A6") (pintype "bidirectional"))
      (node (ref "JP1") (pin "1") (pinfunction "1_1") (pintype "passive"))
    )
    (net (code "65") (name "RAD") (class "Default")
      (node (ref "C38") (pin "2") (pinfunction "2_2") (pintype "passive"))
      (node (ref "C39") (pin "2") (pinfunction "2_2") (pintype "passive"))
      (node (ref "JP3") (pin "3") (pinfunction "3_3") (pintype "passive"))
      (node (ref "R22") (pin "2") (pinfunction "2_2") (pintype "passive"))
    )
    (net (code "66") (name "REF1676") (class "Default")
      (node (ref "C37") (pin "1") (pinfunction "1_1") (pintype "passive"))
      (node (ref "IC2") (pin "5") (pinfunction "REF_5") (pintype "passive"))
    )
    (net (code "67") (name "RLD") (class "Default")
      (node (ref "IC1") (pin "C6") (pinfunction "ECG_EL3_C6") (pintype "bidirectional"))
      (node (ref "JP1") (pin "3") (pinfunction "3_3") (pintype "passive"))
    )
    (net (code "68") (name "RLDD") (class "Default")
      (node (ref "D4") (pin "2") (pinfunction "2_2") (pintype "passive"))
      (node (ref "JP3") (pin "1") (pinfunction "1_1") (pintype "passive"))
      (node (ref "U$4") (pin "2") (pinfunction "2_2") (pintype "passive"))
    )
    (net (code "69") (name "RST") (class "Default")
      (node (ref "C22") (pin "1") (pinfunction "1_1") (pintype "passive"))
      (node (ref "IC3") (pin "E1") (pinfunction "~{RST}_E1") (pintype "bidirectional"))
      (node (ref "IC5") (pin "61") (pinfunction "RSTN_61") (pintype "bidirectional"))
      (node (ref "R5") (pin "1") (pinfunction "1_1") (pintype "passive"))
      (node (ref "SW1") (pin "A") (pinfunction "P_A") (pintype "passive"))
      (node (ref "SW1") (pin "A'") (pinfunction "P1_A'") (pintype "passive"))
    )
    (net (code "70") (name "RTS1") (class "Default")
      (node (ref "IC5") (pin "7") (pinfunction "P1.11_7") (pintype "bidirectional"))
      (node (ref "JP10/FTDI") (pin "6") (pinfunction "6_6") (pintype "passive"))
    )
    (net (code "71") (name "RX0") (class "Default")
      (node (ref "IC5") (pin "42") (pinfunction "P0.9_42") (pintype "bidirectional"))
      (node (ref "IC6") (pin "4") (pinfunction "1Y_4") (pintype "bidirectional"))
    )
    (net (code "72") (name "RX1") (class "Default")
      (node (ref "IC5") (pin "51") (pinfunction "P1.8_51") (pintype "bidirectional"))
      (node (ref "JP4") (pin "4") (pinfunction "4_4") (pintype "passive"))
    )
    (net (code "73") (name "RXBLE") (class "Default")
      (node (ref "IC6") (pin "2") (pinfunction "1I0_2") (pintype "bidirectional"))
      (node (ref "JP6") (pin "5") (pinfunction "5_5") (pintype "passive"))
    )
    (net (code "74") (name "RXFTDI") (class "Default")
      (node (ref "IC6") (pin "3") (pinfunction "1I1_3") (pintype "bidirectional"))
      (node (ref "JP10/FTDI") (pin "5") (pinfunction "5_5") (pintype "passive"))
    )
    (net (code "75") (name "SCL") (class "Default")
      (node (ref "IC3") (pin "F1") (pinfunction "SDA_F1") (pintype "bidirectional"))
      (node (ref "IC4") (pin "4") (pinfunction "SCL_4") (pintype "bidirectional"))
      (node (ref "IC5") (pin "11") (pinfunction "P0.6_11") (pintype "bidirectional"))
      (node (ref "R2") (pin "1") (pinfunction "1_1") (pintype "passive"))
    )
    (net (code "76") (name "SCLK") (class "Default")
      (node (ref "IC1") (pin "E4") (pinfunction "SCLK/SCL_E4") (pintype "bidirectional"))
      (node (ref "IC5") (pin "48") (pinfunction "P0.16_48") (pintype "bidirectional"))
      (node (ref "JP5") (pin "4") (pinfunction "4_4") (pintype "passive"))
      (node (ref "U$1") (pin "SCLK") (pinfunction "SCLK_SCLK") (pintype "bidirectional"))
    )
    (net (code "77") (name "SDA") (class "Default")
      (node (ref "IC3") (pin "F2") (pinfunction "SCL_F2") (pintype "bidirectional"))
      (node (ref "IC4") (pin "1") (pinfunction "SDA_1") (pintype "bidirectional"))
      (node (ref "IC5") (pin "12") (pinfunction "P0.7_12") (pintype "bidirectional"))
      (node (ref "R3") (pin "1") (pinfunction "1_1") (pintype "passive"))
    )
    (net (code "78") (name "SETP") (class "Default")
      (node (ref "IC3") (pin "C5") (pinfunction "SET_C5") (pintype "bidirectional"))
      (node (ref "R1") (pin "2") (pinfunction "2_2") (pintype "passive"))
    )
    (net (code "79") (name "STATE") (class "Default")
      (node (ref "JP2") (pin "2") (pinfunction "2_2") (pintype "passive"))
      (node (ref "JP6") (pin "6") (pinfunction "6_6") (pintype "passive"))
    )
    (net (code "80") (name "SYS") (class "Default")
      (node (ref "C19") (pin "1") (pinfunction "1_1") (pintype "passive"))
      (node (ref "C20") (pin "1") (pinfunction "1_1") (pintype "passive"))
      (node (ref "IC3") (pin "C6") (pinfunction "SYS_1_C6") (pintype "bidirectional"))
      (node (ref "IC3") (pin "D6") (pinfunction "SYS_2_D6") (pintype "bidirectional"))
      (node (ref "Q1") (pin "3") (pinfunction "S_3") (pintype "passive"))
    )
    (net (code "81") (name "THM") (class "Default")
      (node (ref "IC3") (pin "F3") (pinfunction "THM_F3") (pintype "bidirectional"))
      (node (ref "R6") (pin "2") (pinfunction "2_2") (pintype "passive"))
      (node (ref "RT1") (pin "1") (pinfunction "1_1") (pintype "passive"))
    )
    (net (code "82") (name "TRIG") (class "Default")
      (node (ref "IC1") (pin "G6") (pinfunction "TRIG_G6") (pintype "bidirectional"))
      (node (ref "IC5") (pin "49") (pinfunction "P1.7_49") (pintype "bidirectional"))
    )
    (net (code "83") (name "TX0") (class "Default")
      (node (ref "IC5") (pin "41") (pinfunction "P0.8_41") (pintype "bidirectional"))
      (node (ref "IC6") (pin "7") (pinfunction "2Y_7") (pintype "bidirectional"))
    )
    (net (code "84") (name "TX1") (class "Default")
      (node (ref "IC5") (pin "5") (pinfunction "P1.9_5") (pintype "bidirectional"))
      (node (ref "JP4") (pin "3") (pinfunction "3_3") (pintype "passive"))
    )
    (net (code "85") (name "TXBLE") (class "Default")
      (node (ref "IC6") (pin "5") (pinfunction "2I0_5") (pintype "bidirectional"))
      (node (ref "JP6") (pin "4") (pinfunction "4_4") (pintype "passive"))
    )
    (net (code "86") (name "TXFTDI") (class "Default")
      (node (ref "IC6") (pin "6") (pinfunction "2I1_6") (pintype "bidirectional"))
      (node (ref "JP10/FTDI") (pin "4") (pinfunction "4_4") (pintype "passive"))
    )
    (net (code "87") (name "VMID_ECG") (class "Default")
      (node (ref "C1") (pin "2") (pinfunction "2_2") (pintype "passive"))
      (node (ref "IC1") (pin "E6") (pinfunction "VMID_ECG_E6") (pintype "bidirectional"))
    )
    (net (code "88") (name "VREF_ECG") (class "Default")
      (node (ref "C3") (pin "2") (pinfunction "2_2") (pintype "passive"))
      (node (ref "IC1") (pin "F6") (pinfunction "VREF_ECG_F6") (pintype "bidirectional"))
    )
    (net (code "89") (name "VREF_PPG") (class "Default")
      (node (ref "C2") (pin "2") (pinfunction "2_2") (pintype "passive"))
      (node (ref "IC1") (pin "E2") (pinfunction "VREF_PPG_E2") (pintype "bidirectional"))
    )
    (net (code "90") (name "VSIS") (class "Default")
      (node (ref "IC3") (pin "A2") (pinfunction "L1IN_A2") (pintype "bidirectional"))
      (node (ref "IC3") (pin "B2") (pinfunction "L2IN_B2") (pintype "bidirectional"))
      (node (ref "IC3") (pin "C2") (pinfunction "L3IN_C2") (pintype "bidirectional"))
    )
    (net (code "91") (name "WP") (class "Default")
      (node (ref "IC5") (pin "45") (pinfunction "P0.13_45") (pintype "bidirectional"))
      (node (ref "U$1") (pin "WP_N/SIO2") (pinfunction "WP_N/SIO2_WP_N/SIO2") (pintype "bidirectional"))
    )
    (net (code "92") (name "unconnected-(IC1-BIOZ_EL1-PadA3)") (class "Default")
      (node (ref "IC1") (pin "A3") (pinfunction "BIOZ_EL1_A3") (pintype "bidirectional"))
    )
    (net (code "93") (name "unconnected-(IC1-BIOZ_EL2A-PadA1)") (class "Default")
      (node (ref "IC1") (pin "A1") (pinfunction "BIOZ_EL2A_A1") (pintype "bidirectional"))
    )
    (net (code "94") (name "unconnected-(IC1-BIOZ_EL2B-PadB1)") (class "Default")
      (node (ref "IC1") (pin "B1") (pinfunction "BIOZ_EL2B_B1") (pintype "bidirectional"))
    )
    (net (code "95") (name "unconnected-(IC1-BIOZ_EL3A-PadA2)") (class "Default")
      (node (ref "IC1") (pin "A2") (pinfunction "BIOZ_EL3A_A2") (pintype "bidirectional"))
    )
    (net (code "96") (name "unconnected-(IC1-BIOZ_EL3B-PadB2)") (class "Default")
      (node (ref "IC1") (pin "B2") (pinfunction "BIOZ_EL3B_B2") (pintype "bidirectional"))
    )
    (net (code "97") (name "unconnected-(IC1-BIOZ_EL4-PadA4)") (class "Default")
      (node (ref "IC1") (pin "A4") (pinfunction "BIOZ_EL4_A4") (pintype "bidirectional"))
    )
    (net (code "98") (name "unconnected-(IC1-CAL1-PadA5)") (class "Default")
      (node (ref "IC1") (pin "A5") (pinfunction "CAL1_A5") (pintype "bidirectional"))
    )
    (net (code "99") (name "unconnected-(IC1-CAL2-PadB5)") (class "Default")
      (node (ref "IC1") (pin "B5") (pinfunction "CAL2_B5") (pintype "bidirectional"))
    )
    (net (code "100") (name "unconnected-(IC1-CAL3-PadB4)") (class "Default")
      (node (ref "IC1") (pin "B4") (pinfunction "CAL3_B4") (pintype "bidirectional"))
    )
    (net (code "101") (name "unconnected-(IC1-CAL4-PadB3)") (class "Default")
      (node (ref "IC1") (pin "B3") (pinfunction "CAL4_B3") (pintype "bidirectional"))
    )
    (net (code "102") (name "unconnected-(IC1-DRVSJ-PadC5)") (class "Default")
      (node (ref "IC1") (pin "C5") (pinfunction "DRVSJ_C5") (pintype "bidirectional"))
    )
    (net (code "103") (name "unconnected-(IC1-DRVXC-PadD5)") (class "Default")
      (node (ref "IC1") (pin "D5") (pinfunction "DRVXC_D5") (pintype "bidirectional"))
    )
    (net (code "104") (name "unconnected-(IC1-DRVXR-PadC4)") (class "Default")
      (node (ref "IC1") (pin "C4") (pinfunction "DRVXR_C4") (pintype "bidirectional"))
    )
    (net (code "105") (name "unconnected-(IC1-FCLK-PadF5)") (class "Default")
      (node (ref "IC1") (pin "F5") (pinfunction "FCLK_F5") (pintype "bidirectional"))
    )
    (net (code "106") (name "unconnected-(IC1-LDO_OUT-PadE7)") (class "Default")
      (node (ref "IC1") (pin "E7") (pinfunction "LDO_OUT_E7") (pintype "bidirectional"))
    )
    (net (code "107") (name "unconnected-(IC1-LED4_DRV-PadF2)") (class "Default")
      (node (ref "IC1") (pin "F2") (pinfunction "LED4_DRV_F2") (pintype "bidirectional"))
    )
    (net (code "108") (name "unconnected-(IC1-LED5_DRV-PadG1)") (class "Default")
      (node (ref "IC1") (pin "G1") (pinfunction "LED5_DRV_G1") (pintype "bidirectional"))
    )
    (net (code "109") (name "unconnected-(IC1-LED6_DRV-PadF1)") (class "Default")
      (node (ref "IC1") (pin "F1") (pinfunction "LED6_DRV_F1") (pintype "bidirectional"))
    )
    (net (code "110") (name "unconnected-(IC1-PD4_IN-PadC2)") (class "Default")
      (node (ref "IC1") (pin "C2") (pinfunction "PD4_IN_C2") (pintype "bidirectional"))
    )
    (net (code "111") (name "unconnected-(IC1-RLD_INV-PadC7)") (class "Default")
      (node (ref "IC1") (pin "C7") (pinfunction "RLD_INV_C7") (pintype "bidirectional"))
    )
    (net (code "112") (name "unconnected-(IC3-B1LX-PadF6)") (class "Default")
      (node (ref "IC3") (pin "F6") (pinfunction "B1LX_F6") (pintype "bidirectional"))
    )
    (net (code "113") (name "unconnected-(IC3-B1OUT-PadF5)") (class "Default")
      (node (ref "IC3") (pin "F5") (pinfunction "B1OUT_F5") (pintype "bidirectional"))
    )
    (net (code "114") (name "unconnected-(IC3-B2LX-PadA6)") (class "Default")
      (node (ref "IC3") (pin "A6") (pinfunction "B2LX_A6") (pintype "bidirectional"))
    )
    (net (code "115") (name "unconnected-(IC3-B2OUT-PadA5)") (class "Default")
      (node (ref "IC3") (pin "A5") (pinfunction "B2OUT_A5") (pintype "bidirectional"))
    )
    (net (code "116") (name "unconnected-(IC5-ADC0_RDY-Pad68)") (class "Default")
      (node (ref "IC5") (pin "68") (pinfunction "ADC0_RDY_68") (pintype "bidirectional"))
    )
    (net (code "117") (name "unconnected-(IC5-ADC1_RDY-Pad1)") (class "Default")
      (node (ref "IC5") (pin "1") (pinfunction "ADC1_RDY_1") (pintype "bidirectional"))
    )
    (net (code "118") (name "unconnected-(IC5-AIN0-Pad20)") (class "Default")
      (node (ref "IC5") (pin "20") (pinfunction "AIN0_20") (pintype "bidirectional"))
    )
    (net (code "119") (name "unconnected-(IC5-AIN1-Pad21)") (class "Default")
      (node (ref "IC5") (pin "21") (pinfunction "AIN1_21") (pintype "bidirectional"))
    )
    (net (code "120") (name "unconnected-(IC5-AIN2-Pad22)") (class "Default")
      (node (ref "IC5") (pin "22") (pinfunction "AIN2_22") (pintype "bidirectional"))
    )
    (net (code "121") (name "unconnected-(IC5-AIN3-Pad23)") (class "Default")
      (node (ref "IC5") (pin "23") (pinfunction "AIN3_23") (pintype "bidirectional"))
    )
    (net (code "122") (name "unconnected-(IC5-AIN4-Pad24)") (class "Default")
      (node (ref "IC5") (pin "24") (pinfunction "AIN4_24") (pintype "bidirectional"))
    )
    (net (code "123") (name "unconnected-(IC5-AIN5-Pad25)") (class "Default")
      (node (ref "IC5") (pin "25") (pinfunction "AIN5_25") (pintype "bidirectional"))
    )
    (net (code "124") (name "unconnected-(IC5-AIN6-Pad28)") (class "Default")
      (node (ref "IC5") (pin "28") (pinfunction "AIN6_28") (pintype "bidirectional"))
    )
    (net (code "125") (name "unconnected-(IC5-AIN7-Pad29)") (class "Default")
      (node (ref "IC5") (pin "29") (pinfunction "AIN7_29") (pintype "bidirectional"))
    )
    (net (code "126") (name "unconnected-(IC5-AIN8-Pad31)") (class "Default")
      (node (ref "IC5") (pin "31") (pinfunction "AIN8_31") (pintype "bidirectional"))
    )
    (net (code "127") (name "unconnected-(IC5-AIN9-Pad32)") (class "Default")
      (node (ref "IC5") (pin "32") (pinfunction "AIN9_32") (pintype "bidirectional"))
    )
    (net (code "128") (name "unconnected-(IC5-AIN10-Pad33)") (class "Default")
      (node (ref "IC5") (pin "33") (pinfunction "AIN10_33") (pintype "bidirectional"))
    )
    (net (code "129") (name "unconnected-(IC5-AIN11-Pad34)") (class "Default")
      (node (ref "IC5") (pin "34") (pinfunction "AIN11_34") (pintype "bidirectional"))
    )
    (net (code "130") (name "unconnected-(IC5-FSK_IN-Pad3)") (class "Default")
      (node (ref "IC5") (pin "3") (pinfunction "FSK_IN_3") (pintype "bidirectional"))
    )
    (net (code "131") (name "unconnected-(IC5-FSK_OUT-Pad4)") (class "Default")
      (node (ref "IC5") (pin "4") (pinfunction "FSK_OUT_4") (pintype "bidirectional"))
    )
    (net (code "132") (name "unconnected-(IC5-INT_REF-Pad39)") (class "Default")
      (node (ref "IC5") (pin "39") (pinfunction "INT_REF_39") (pintype "bidirectional"))
    )
    (net (code "133") (name "unconnected-(IC5-N.C.-Pad13)") (class "Default")
      (node (ref "IC5") (pin "13") (pinfunction "N.C._13") (pintype "bidirectional"))
    )
    (net (code "134") (name "unconnected-(IC5-N.C.2-Pad14)") (class "Default")
      (node (ref "IC5") (pin "14") (pinfunction "N.C.2_14") (pintype "bidirectional"))
    )
    (net (code "135") (name "unconnected-(IC5-N.C.3-Pad18)") (class "Default")
      (node (ref "IC5") (pin "18") (pinfunction "N.C.3_18") (pintype "bidirectional"))
    )
    (net (code "136") (name "unconnected-(IC5-N.C.4-Pad50)") (class "Default")
      (node (ref "IC5") (pin "50") (pinfunction "N.C.4_50") (pintype "bidirectional"))
    )
    (net (code "137") (name "unconnected-(IC5-N.C.5-Pad52)") (class "Default")
      (node (ref "IC5") (pin "52") (pinfunction "N.C.5_52") (pintype "bidirectional"))
    )
    (net (code "138") (name "unconnected-(IC5-N.C.6-Pad56)") (class "Default")
      (node (ref "IC5") (pin "56") (pinfunction "N.C.6_56") (pintype "bidirectional"))
    )
    (net (code "139") (name "unconnected-(IC5-N.C.7-Pad67)") (class "Default")
      (node (ref "IC5") (pin "67") (pinfunction "N.C.7_67") (pintype "bidirectional"))
    )
    (net (code "140") (name "unconnected-(IC5-P0.0-Pad9)") (class "Default")
      (node (ref "IC5") (pin "9") (pinfunction "P0.0_9") (pintype "bidirectional"))
    )
    (net (code "141") (name "unconnected-(IC5-P0.1-Pad10)") (class "Default")
      (node (ref "IC5") (pin "10") (pinfunction "P0.1_10") (pintype "bidirectional"))
    )
    (net (code "142") (name "unconnected-(IC5-P0.21-Pad66)") (class "Default")
      (node (ref "IC5") (pin "66") (pinfunction "P0.21_66") (pintype "bidirectional"))
    )
    (net (code "143") (name "unconnected-(IC5-P0.31-Pad57)") (class "Default")
      (node (ref "IC5") (pin "57") (pinfunction "P0.31_57") (pintype "bidirectional"))
    )
    (net (code "144") (name "unconnected-(IC5-P1.12-Pad8)") (class "Default")
      (node (ref "IC5") (pin "8") (pinfunction "P1.12_8") (pintype "bidirectional"))
    )
    (net (code "145") (name "unconnected-(IC5-REF0N-Pad19)") (class "Default")
      (node (ref "IC5") (pin "19") (pinfunction "REF0N_19") (pintype "bidirectional"))
    )
    (net (code "146") (name "unconnected-(IC5-REF0P-Pad17)") (class "Default")
      (node (ref "IC5") (pin "17") (pinfunction "REF0P_17") (pintype "bidirectional"))
    )
    (net (code "147") (name "unconnected-(IC5-REF1N-Pad35)") (class "Default")
      (node (ref "IC5") (pin "35") (pinfunction "REF1N_35") (pintype "bidirectional"))
    )
    (net (code "148") (name "unconnected-(IC5-REF1P-Pad36)") (class "Default")
      (node (ref "IC5") (pin "36") (pinfunction "REF1P_36") (pintype "bidirectional"))
    )
    (net (code "149") (name "unconnected-(IC5-VREG1-Pad58)") (class "Default")
      (node (ref "IC5") (pin "58") (pinfunction "VREG1_58") (pintype "bidirectional"))
    )
    (net (code "150") (name "unconnected-(IC6-3I0-Pad11)") (class "Default")
      (node (ref "IC6") (pin "11") (pinfunction "3I0_11") (pintype "bidirectional"))
    )
    (net (code "151") (name "unconnected-(IC6-3I1-Pad10)") (class "Default")
      (node (ref "IC6") (pin "10") (pinfunction "3I1_10") (pintype "bidirectional"))
    )
    (net (code "152") (name "unconnected-(IC6-3Y-Pad9)") (class "Default")
      (node (ref "IC6") (pin "9") (pinfunction "3Y_9") (pintype "bidirectional"))
    )
    (net (code "153") (name "unconnected-(IC6-4I0-Pad14)") (class "Default")
      (node (ref "IC6") (pin "14") (pinfunction "4I0_14") (pintype "bidirectional"))
    )
    (net (code "154") (name "unconnected-(IC6-4I1-Pad13)") (class "Default")
      (node (ref "IC6") (pin "13") (pinfunction "4I1_13") (pintype "bidirectional"))
    )
    (net (code "155") (name "unconnected-(IC6-4Y-Pad12)") (class "Default")
      (node (ref "IC6") (pin "12") (pinfunction "4Y_12") (pintype "bidirectional"))
    )
    (net (code "156") (name "unconnected-(LED1-NC-Pad6)") (class "Default")
      (node (ref "LED1") (pin "6") (pinfunction "NC_6") (pintype "no_connect"))
    )
    (net (code "157") (name "unconnected-(U$2-Pad2)") (class "Default")
      (node (ref "U$2") (pin "2") (pinfunction "2_2") (pintype "input"))
    )
    (net (code "158") (name "unconnected-(U$2-Pad3)") (class "Default")
      (node (ref "U$2") (pin "3") (pinfunction "3_3") (pintype "input"))
    )
    (net (code "159") (name "unconnected-(U$2-Pad4)") (class "Default")
      (node (ref "U$2") (pin "4") (pinfunction "4_4") (pintype "input"))
    )
  )
)
